# rfm69hcw-breakout.net
KiCad netlist of a schematic drawn in EAGLE
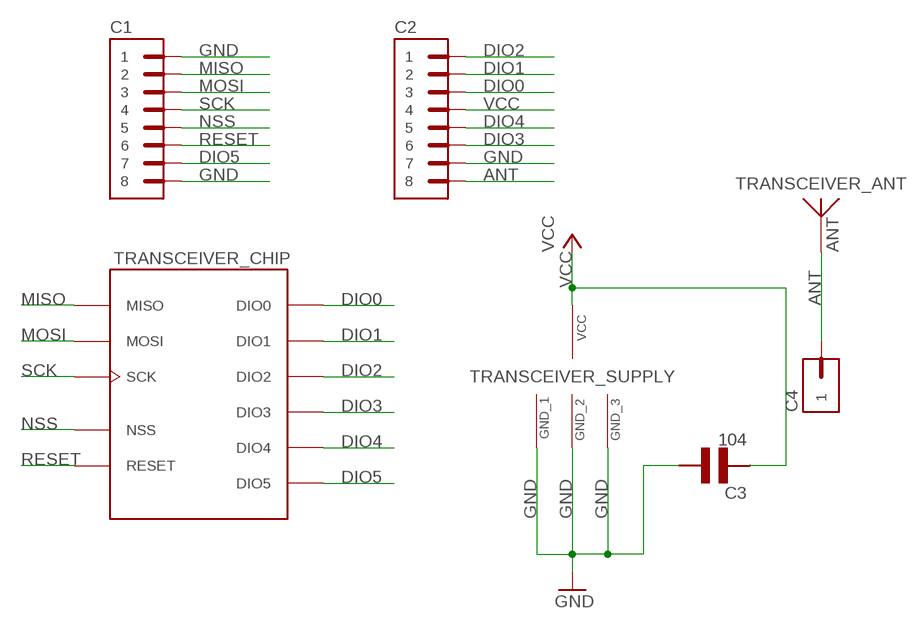
[diagram p0: schematic, sheet 1]

(export (version "E")
  (design (tool "Eeschema 10.0.6"))
  (components
    (comp (ref "C1")
      (value "PIN_HEADER_8-WIDE")
      (footprint "eagle-import:BREAKAWAY_STRAIGHT_8_WIDE")
      (libsource (lib "eagle-import") (part "PIN_HEADER_8-WIDE"))
    )
    (comp (ref "C2")
      (value "PIN_HEADER_8-WIDE")
      (footprint "eagle-import:BREAKAWAY_STRAIGHT_8_WIDE")
      (libsource (lib "eagle-import") (part "PIN_HEADER_8-WIDE"))
    )
    (comp (ref "C3")
      (value "104")
      (footprint "eagle-import:CERAMIC_CAP_5MM")
      (libsource (lib "eagle-import") (part "CAPACITOR-CERAMIC-5MM"))
    )
    (comp (ref "C4")
      (value "PIN_HEADER_1-WIDE")
      (footprint "eagle-import:BREAKAWAY_STRAIGHT_1_WIDE")
      (libsource (lib "eagle-import") (part "PIN_HEADER_1-WIDE"))
    )
    (comp (ref "TRANSCEIVER")
      (value "RFM69HCW-S2")
      (footprint "eagle-import:HOPE-RF-16")
      (libsource (lib "eagle-import") (part "RFM69HCW-S2"))
    )
  )
  (nets
    (net (code "1") (name "/ANT") (class "Default")
      (node (ref "C2") (pin "8") (pinfunction "8_8") (pintype "bidirectional"))
      (node (ref "C4") (pin "1") (pinfunction "1_1") (pintype "bidirectional"))
      (node (ref "TRANSCEIVER") (pin "ANT") (pinfunction "ANT_ANT") (pintype "passive"))
    )
    (net (code "2") (name "/DIO0") (class "Default")
      (node (ref "C2") (pin "3") (pinfunction "3_3") (pintype "bidirectional"))
      (node (ref "TRANSCEIVER") (pin "DIO0") (pinfunction "DIO0_DIO0") (pintype "bidirectional"))
    )
    (net (code "3") (name "/DIO1") (class "Default")
      (node (ref "C2") (pin "2") (pinfunction "2_2") (pintype "bidirectional"))
      (node (ref "TRANSCEIVER") (pin "DIO1") (pinfunction "DIO1_DIO1") (pintype "bidirectional"))
    )
    (net (code "4") (name "/DIO2") (class "Default")
      (node (ref "C2") (pin "1") (pinfunction "1_1") (pintype "bidirectional"))
      (node (ref "TRANSCEIVER") (pin "DIO2") (pinfunction "DIO2_DIO2") (pintype "bidirectional"))
    )
    (net (code "5") (name "/DIO3") (class "Default")
      (node (ref "C2") (pin "6") (pinfunction "6_6") (pintype "bidirectional"))
      (node (ref "TRANSCEIVER") (pin "DIO3") (pinfunction "DIO3_DIO3") (pintype "bidirectional"))
    )
    (net (code "6") (name "/DIO4") (class "Default")
      (node (ref "C2") (pin "5") (pinfunction "5_5") (pintype "bidirectional"))
      (node (ref "TRANSCEIVER") (pin "DIO4") (pinfunction "DIO4_DIO4") (pintype "bidirectional"))
    )
    (net (code "7") (name "/DIO5") (class "Default")
      (node (ref "C1") (pin "7") (pinfunction "7_7") (pintype "bidirectional"))
      (node (ref "TRANSCEIVER") (pin "DIO5") (pinfunction "DIO5_DIO5") (pintype "bidirectional"))
    )
    (net (code "8") (name "/MISO") (class "Default")
      (node (ref "C1") (pin "2") (pinfunction "2_2") (pintype "bidirectional"))
      (node (ref "TRANSCEIVER") (pin "MISO") (pinfunction "MISO_MISO") (pintype "input"))
    )
    (net (code "9") (name "/MOSI") (class "Default")
      (node (ref "C1") (pin "3") (pinfunction "3_3") (pintype "bidirectional"))
      (node (ref "TRANSCEIVER") (pin "MOSI") (pinfunction "MOSI_MOSI") (pintype "output"))
    )
    (net (code "10") (name "/NSS") (class "Default")
      (node (ref "C1") (pin "5") (pinfunction "5_5") (pintype "bidirectional"))
      (node (ref "TRANSCEIVER") (pin "NSS") (pinfunction "NSS_NSS") (pintype "input"))
    )
    (net (code "11") (name "/RESET") (class "Default")
      (node (ref "C1") (pin "6") (pinfunction "6_6") (pintype "bidirectional"))
      (node (ref "TRANSCEIVER") (pin "RESET") (pinfunction "RESET_RESET") (pintype "bidirectional"))
    )
    (net (code "12") (name "/SCK") (class "Default")
      (node (ref "C1") (pin "4") (pinfunction "4_4") (pintype "bidirectional"))
      (node (ref "TRANSCEIVER") (pin "SCK") (pinfunction "SCK_SCK") (pintype "input"))
    )
    (net (code "13") (name "GND") (class "Default")
      (node (ref "C1") (pin "1") (pinfunction "1_1") (pintype "bidirectional"))
      (node (ref "C1") (pin "8") (pinfunction "8_8") (pintype "bidirectional"))
      (node (ref "C2") (pin "7") (pinfunction "7_7") (pintype "bidirectional"))
      (node (ref "C3") (pin "P$2") (pinfunction "P$2_P$2") (pintype "passive"))
      (node (ref "TRANSCEIVER") (pin "GND1") (pinfunction "GND_1_GND1") (pintype "power_in"))
      (node (ref "TRANSCEIVER") (pin "GND2") (pinfunction "GND_2_GND2") (pintype "power_in"))
      (node (ref "TRANSCEIVER") (pin "GND3") (pinfunction "GND_3_GND3") (pintype "power_in"))
    )
    (net (code "14") (name "VCC") (class "Default")
      (node (ref "C2") (pin "4") (pinfunction "4_4") (pintype "bidirectional"))
      (node (ref "C3") (pin "P$1") (pinfunction "P$1_P$1") (pintype "passive"))
      (node (ref "TRANSCEIVER") (pin "3.3V") (pinfunction "VCC_3.3V") (pintype "power_in"))
    )
  )
)
